# Schematic_final.net
KiCad netlist of a schematic drawn in EAGLE
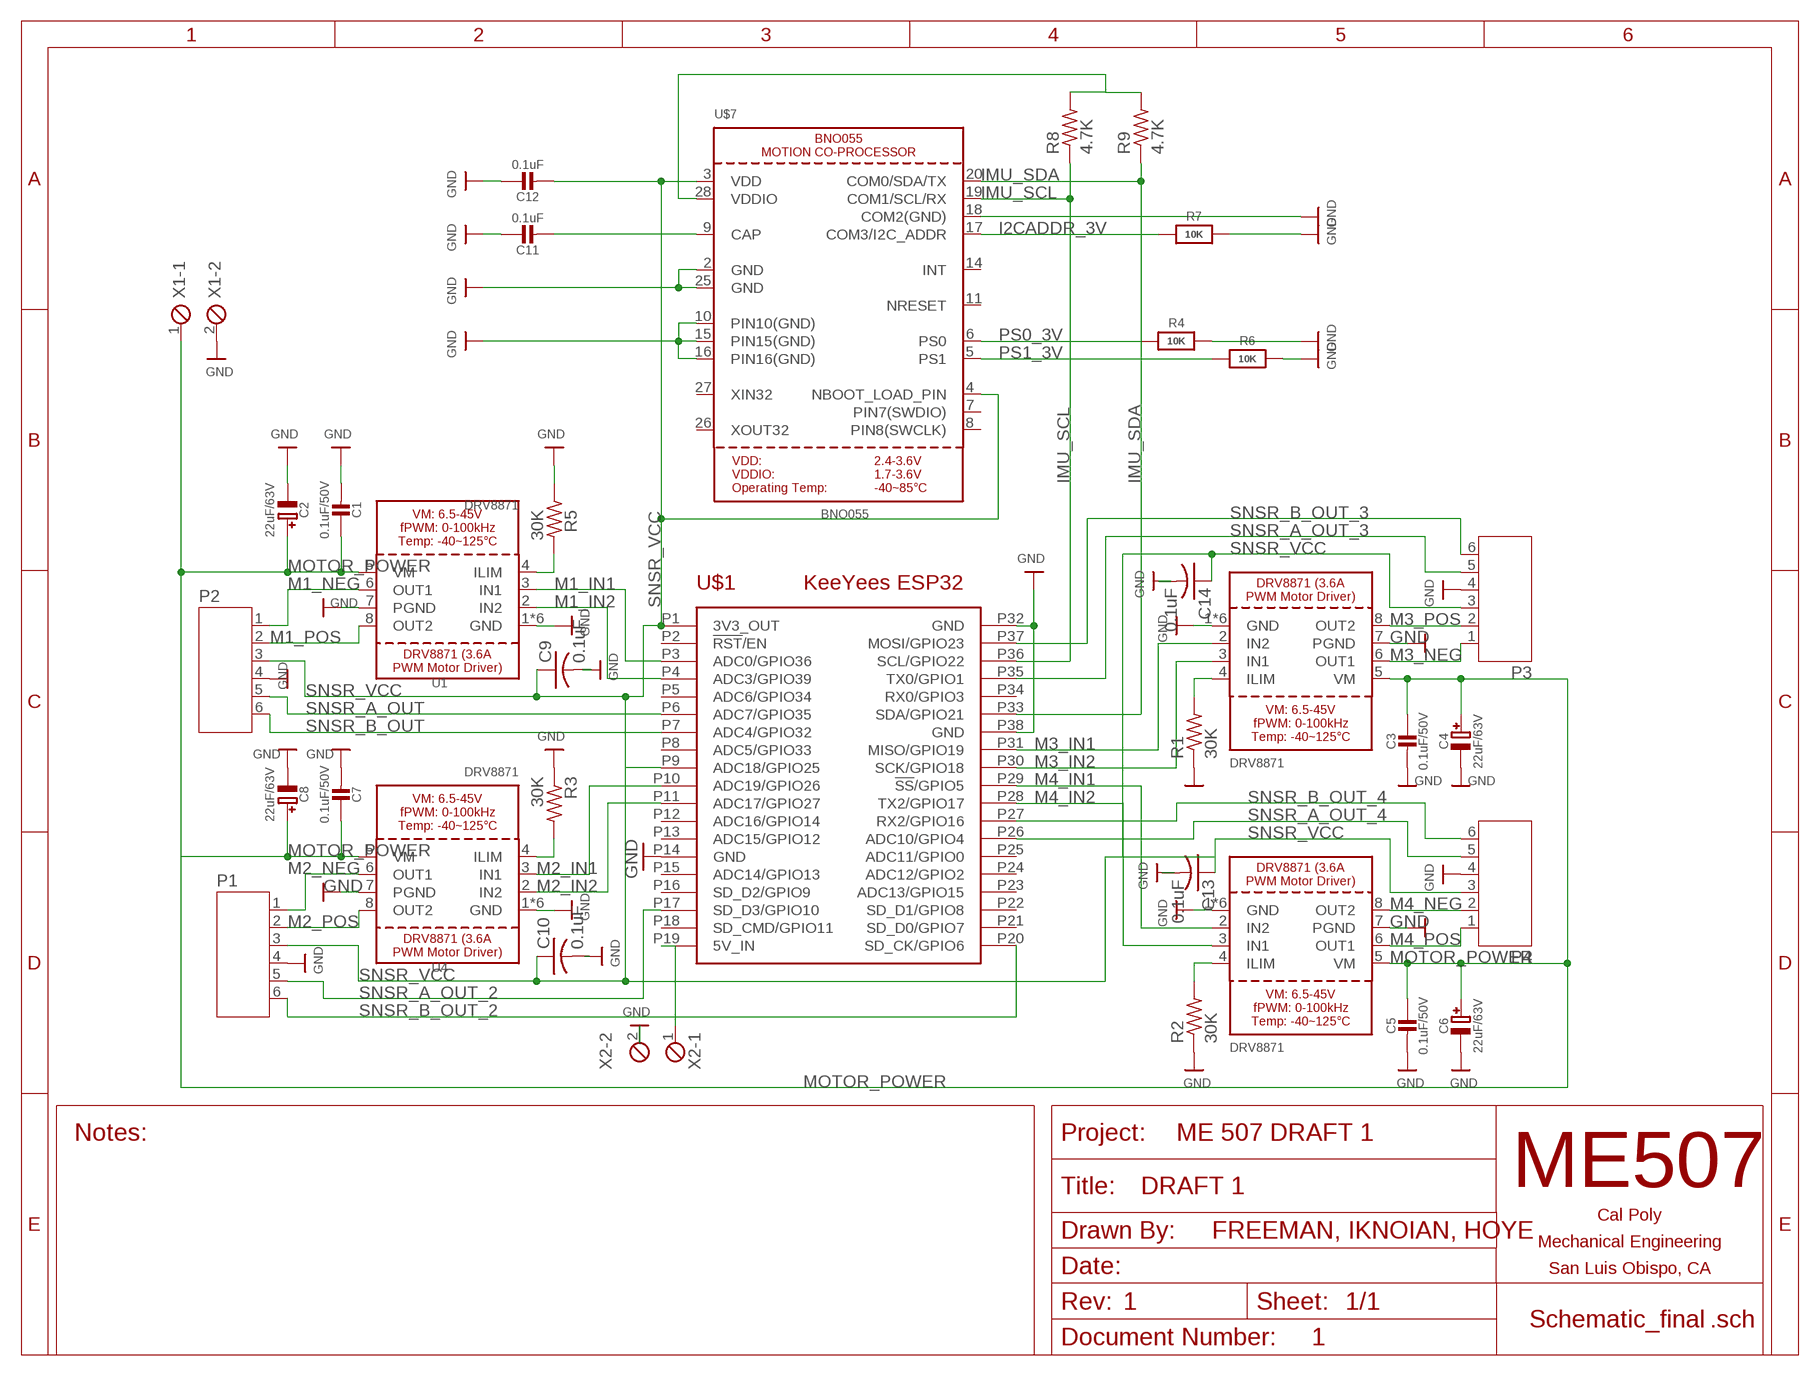
[diagram p0: schematic, sheet 1]

(export (version "E")
  (design (tool "Eeschema 10.0.6"))
  (components
    (comp (ref "C1")
      (value "0.1uF/50V")
      (footprint "eagle-import:0805-NO")
      (libsource (lib "eagle-import") (part "CAP_CERAMIC0805-NOOUTLINE"))
    )
    (comp (ref "C2")
      (value "22uF/63V")
      (footprint "eagle-import:PANASONIC_D")
      (libsource (lib "eagle-import") (part "CAP_ELECTROLYTICPANASONIC_D"))
    )
    (comp (ref "C3")
      (value "0.1uF/50V")
      (footprint "eagle-import:0805-NO")
      (libsource (lib "eagle-import") (part "CAP_CERAMIC0805-NOOUTLINE"))
    )
    (comp (ref "C4")
      (value "22uF/63V")
      (footprint "eagle-import:PANASONIC_D")
      (libsource (lib "eagle-import") (part "CAP_ELECTROLYTICPANASONIC_D"))
    )
    (comp (ref "C5")
      (value "0.1uF/50V")
      (footprint "eagle-import:0805-NO")
      (libsource (lib "eagle-import") (part "CAP_CERAMIC0805-NOOUTLINE"))
    )
    (comp (ref "C6")
      (value "22uF/63V")
      (footprint "eagle-import:PANASONIC_D")
      (libsource (lib "eagle-import") (part "CAP_ELECTROLYTICPANASONIC_D"))
    )
    (comp (ref "C7")
      (value "0.1uF/50V")
      (footprint "eagle-import:0805-NO")
      (libsource (lib "eagle-import") (part "CAP_CERAMIC0805-NOOUTLINE"))
    )
    (comp (ref "C8")
      (value "22uF/63V")
      (footprint "eagle-import:PANASONIC_D")
      (libsource (lib "eagle-import") (part "CAP_ELECTROLYTICPANASONIC_D"))
    )
    (comp (ref "C9")
      (value "0.1uF")
      (footprint "eagle-import:C025-030X050")
      (libsource (lib "eagle-import") (part "C-US025-030X050"))
    )
    (comp (ref "C10")
      (value "0.1uF")
      (footprint "eagle-import:C025-030X050")
      (libsource (lib "eagle-import") (part "C-US025-030X050"))
    )
    (comp (ref "C11")
      (value "0.1uF")
      (footprint "eagle-import:0805-NO")
      (libsource (lib "eagle-import") (part "CAP_CERAMIC0805-NOOUTLINE"))
    )
    (comp (ref "C12")
      (value "0.1uF")
      (footprint "eagle-import:0805_10MGAP")
      (libsource (lib "eagle-import") (part "CAP_CERAMIC0805_10MGAP"))
    )
    (comp (ref "C13")
      (value "0.1uF")
      (footprint "eagle-import:C025-030X050")
      (libsource (lib "eagle-import") (part "C-US025-030X050"))
    )
    (comp (ref "C14")
      (value "0.1uF")
      (footprint "eagle-import:C025-030X050")
      (libsource (lib "eagle-import") (part "C-US025-030X050"))
    )
    (comp (ref "P1")
      (value "JST-PH6")
      (footprint "eagle-import:JST-PH6")
      (libsource (lib "eagle-import") (part "JST-PH6"))
    )
    (comp (ref "P2")
      (value "JST-PH6")
      (footprint "eagle-import:JST-PH6")
      (libsource (lib "eagle-import") (part "JST-PH6"))
    )
    (comp (ref "P3")
      (value "JST-PH6")
      (footprint "eagle-import:JST-PH6")
      (libsource (lib "eagle-import") (part "JST-PH6"))
    )
    (comp (ref "P4")
      (value "JST-PH6")
      (footprint "eagle-import:JST-PH6")
      (libsource (lib "eagle-import") (part "JST-PH6"))
    )
    (comp (ref "R1")
      (value "30K")
      (footprint "eagle-import:0805-THM")
      (libsource (lib "eagle-import") (part "FLIPFLOP-RES"))
    )
    (comp (ref "R2")
      (value "30K")
      (footprint "eagle-import:0805-THM")
      (libsource (lib "eagle-import") (part "FLIPFLOP-RES"))
    )
    (comp (ref "R3")
      (value "30K")
      (footprint "eagle-import:0805-THM")
      (libsource (lib "eagle-import") (part "FLIPFLOP-RES"))
    )
    (comp (ref "R4")
      (value "10K")
      (footprint "eagle-import:0805-NO")
      (libsource (lib "eagle-import") (part "RESISTOR0805_NOOUTLINE"))
    )
    (comp (ref "R5")
      (value "30K")
      (footprint "eagle-import:0805-THM")
      (libsource (lib "eagle-import") (part "FLIPFLOP-RES"))
    )
    (comp (ref "R6")
      (value "10K")
      (footprint "eagle-import:0805-NO")
      (libsource (lib "eagle-import") (part "RESISTOR0805_NOOUTLINE"))
    )
    (comp (ref "R7")
      (value "10K")
      (footprint "eagle-import:0805-NO")
      (libsource (lib "eagle-import") (part "RESISTOR0805_NOOUTLINE"))
    )
    (comp (ref "R8")
      (value "4.7K")
      (footprint "eagle-import:R0805")
      (libsource (lib "eagle-import") (part "R-US_R0805"))
    )
    (comp (ref "R9")
      (value "4.7K")
      (footprint "eagle-import:R0805")
      (libsource (lib "eagle-import") (part "R-US_R0805"))
    )
    (comp (ref "U$1")
      (value "KEEYEES_ESP32")
      (footprint "eagle-import:KEEYEES_ESP32")
      (libsource (lib "eagle-import") (part "KEEYEES_ESP32"))
    )
    (comp (ref "U$7")
      (value "BNO055")
      (footprint "eagle-import:BNO055")
      (libsource (lib "eagle-import") (part "BNO055"))
    )
    (comp (ref "U1")
      (value "DRV8871")
      (footprint "eagle-import:HSOP8")
      (libsource (lib "eagle-import") (part "DRV8871"))
    )
    (comp (ref "U2")
      (value "DRV8871")
      (footprint "eagle-import:HSOP8")
      (libsource (lib "eagle-import") (part "DRV8871"))
    )
    (comp (ref "U3")
      (value "DRV8871")
      (footprint "eagle-import:HSOP8")
      (libsource (lib "eagle-import") (part "DRV8871"))
    )
    (comp (ref "U4")
      (value "DRV8871")
      (footprint "eagle-import:HSOP8")
      (libsource (lib "eagle-import") (part "DRV8871"))
    )
    (comp (ref "X1")
      (value "SCREWTERM_2P_254")
      (footprint "eagle-import:2POL254")
      (libsource (lib "eagle-import") (part "SCREWTERM_2P_254"))
    )
    (comp (ref "X2")
      (value "SCREWTERM_2P_254")
      (footprint "eagle-import:2POL254")
      (libsource (lib "eagle-import") (part "SCREWTERM_2P_254"))
    )
  )
  (nets
    (net (code "1") (name "/I2CADDR_3V") (class "Default")
      (node (ref "R7") (pin "1") (pinfunction "1_1") (pintype "passive"))
      (node (ref "U$7") (pin "17") (pinfunction "COM3/I2C_ADDR_17") (pintype "bidirectional"))
    )
    (net (code "2") (name "/IMU_SCL") (class "Default")
      (node (ref "R8") (pin "1") (pinfunction "1_1") (pintype "passive"))
      (node (ref "U$1") (pin "P36") (pinfunction "SCL/GPIO22_P36") (pintype "bidirectional"))
      (node (ref "U$7") (pin "19") (pinfunction "COM1/SCL/RX_19") (pintype "bidirectional"))
    )
    (net (code "3") (name "/IMU_SDA") (class "Default")
      (node (ref "R9") (pin "1") (pinfunction "1_1") (pintype "passive"))
      (node (ref "U$1") (pin "P33") (pinfunction "SDA/GPIO21_P33") (pintype "bidirectional"))
      (node (ref "U$7") (pin "20") (pinfunction "COM0/SDA/TX_20") (pintype "bidirectional"))
    )
    (net (code "4") (name "/M1_IN1") (class "Default")
      (node (ref "U$1") (pin "P3") (pinfunction "ADC0/GPIO36_P3") (pintype "bidirectional"))
      (node (ref "U1") (pin "3") (pinfunction "IN1_3") (pintype "input"))
    )
    (net (code "5") (name "/M1_IN2") (class "Default")
      (node (ref "U$1") (pin "P4") (pinfunction "ADC3/GPIO39_P4") (pintype "bidirectional"))
      (node (ref "U1") (pin "2") (pinfunction "IN2_2") (pintype "input"))
    )
    (net (code "6") (name "/M1_NEG") (class "Default")
      (node (ref "P2") (pin "1") (pinfunction "1_1") (pintype "passive"))
      (node (ref "U1") (pin "6") (pinfunction "OUT1_6") (pintype "output"))
    )
    (net (code "7") (name "/M1_POS") (class "Default")
      (node (ref "P2") (pin "2") (pinfunction "2_2") (pintype "passive"))
      (node (ref "U1") (pin "8") (pinfunction "OUT2_8") (pintype "output"))
    )
    (net (code "8") (name "/M2_IN1") (class "Default")
      (node (ref "U$1") (pin "P10") (pinfunction "ADC19/GPIO26_P10") (pintype "bidirectional"))
      (node (ref "U4") (pin "3") (pinfunction "IN1_3") (pintype "input"))
    )
    (net (code "9") (name "/M2_IN2") (class "Default")
      (node (ref "U$1") (pin "P11") (pinfunction "ADC17/GPIO27_P11") (pintype "bidirectional"))
      (node (ref "U4") (pin "2") (pinfunction "IN2_2") (pintype "input"))
    )
    (net (code "10") (name "/M2_NEG") (class "Default")
      (node (ref "P1") (pin "1") (pinfunction "1_1") (pintype "passive"))
      (node (ref "U4") (pin "6") (pinfunction "OUT1_6") (pintype "output"))
    )
    (net (code "11") (name "/M2_POS") (class "Default")
      (node (ref "P1") (pin "2") (pinfunction "2_2") (pintype "passive"))
      (node (ref "U4") (pin "8") (pinfunction "OUT2_8") (pintype "output"))
    )
    (net (code "12") (name "/M3_IN1") (class "Default")
      (node (ref "U$1") (pin "P31") (pinfunction "MISO/GPIO19_P31") (pintype "bidirectional"))
      (node (ref "U2") (pin "2") (pinfunction "IN2_2") (pintype "input"))
    )
    (net (code "13") (name "/M3_IN2") (class "Default")
      (node (ref "U$1") (pin "P30") (pinfunction "SCK/GPIO18_P30") (pintype "bidirectional"))
      (node (ref "U2") (pin "3") (pinfunction "IN1_3") (pintype "input"))
    )
    (net (code "14") (name "/M3_NEG") (class "Default")
      (node (ref "P3") (pin "1") (pinfunction "1_1") (pintype "passive"))
      (node (ref "U2") (pin "6") (pinfunction "OUT1_6") (pintype "output"))
    )
    (net (code "15") (name "/M3_POS") (class "Default")
      (node (ref "P3") (pin "2") (pinfunction "2_2") (pintype "passive"))
      (node (ref "U2") (pin "8") (pinfunction "OUT2_8") (pintype "output"))
    )
    (net (code "16") (name "/M4_IN1") (class "Default")
      (node (ref "U$1") (pin "P29") (pinfunction "~{SS}/GPIO5_P29") (pintype "bidirectional"))
      (node (ref "U3") (pin "2") (pinfunction "IN2_2") (pintype "input"))
    )
    (net (code "17") (name "/M4_IN2") (class "Default")
      (node (ref "U$1") (pin "P28") (pinfunction "TX2/GPIO17_P28") (pintype "bidirectional"))
      (node (ref "U3") (pin "3") (pinfunction "IN1_3") (pintype "input"))
    )
    (net (code "18") (name "/M4_NEG") (class "Default")
      (node (ref "P4") (pin "2") (pinfunction "2_2") (pintype "passive"))
      (node (ref "U3") (pin "8") (pinfunction "OUT2_8") (pintype "output"))
    )
    (net (code "19") (name "/M4_POS") (class "Default")
      (node (ref "P4") (pin "1") (pinfunction "1_1") (pintype "passive"))
      (node (ref "U3") (pin "6") (pinfunction "OUT1_6") (pintype "output"))
    )
    (net (code "20") (name "/MOTOR_POWER") (class "Default")
      (node (ref "C1") (pin "1") (pinfunction "1_1") (pintype "passive"))
      (node (ref "C2") (pin "+") (pinfunction "+_+") (pintype "passive"))
      (node (ref "C3") (pin "1") (pinfunction "1_1") (pintype "passive"))
      (node (ref "C4") (pin "+") (pinfunction "+_+") (pintype "passive"))
      (node (ref "C5") (pin "1") (pinfunction "1_1") (pintype "passive"))
      (node (ref "C6") (pin "+") (pinfunction "+_+") (pintype "passive"))
      (node (ref "C7") (pin "1") (pinfunction "1_1") (pintype "passive"))
      (node (ref "C8") (pin "+") (pinfunction "+_+") (pintype "passive"))
      (node (ref "U1") (pin "5") (pinfunction "VM_5") (pintype "power_in"))
      (node (ref "U2") (pin "5") (pinfunction "VM_5") (pintype "power_in"))
      (node (ref "U3") (pin "5") (pinfunction "VM_5") (pintype "power_in"))
      (node (ref "U4") (pin "5") (pinfunction "VM_5") (pintype "power_in"))
      (node (ref "X1") (pin "1") (pinfunction "1_1") (pintype "passive"))
    )
    (net (code "21") (name "/PS0_3V") (class "Default")
      (node (ref "R4") (pin "1") (pinfunction "1_1") (pintype "passive"))
      (node (ref "U$7") (pin "6") (pinfunction "PS0_6") (pintype "input"))
    )
    (net (code "22") (name "/PS1_3V") (class "Default")
      (node (ref "R6") (pin "1") (pinfunction "1_1") (pintype "passive"))
      (node (ref "U$7") (pin "5") (pinfunction "PS1_5") (pintype "input"))
    )
    (net (code "23") (name "/SNSR_A_OUT") (class "Default")
      (node (ref "P2") (pin "5") (pinfunction "5_5") (pintype "passive"))
      (node (ref "U$1") (pin "P6") (pinfunction "ADC7/GPIO35_P6") (pintype "bidirectional"))
    )
    (net (code "24") (name "/SNSR_A_OUT_2") (class "Default")
      (node (ref "P1") (pin "5") (pinfunction "5_5") (pintype "passive"))
      (node (ref "U$1") (pin "P17") (pinfunction "SD_D3/GPIO10_P17") (pintype "bidirectional"))
    )
    (net (code "25") (name "/SNSR_A_OUT_3") (class "Default")
      (node (ref "P3") (pin "5") (pinfunction "5_5") (pintype "passive"))
      (node (ref "U$1") (pin "P35") (pinfunction "TX0/GPIO1_P35") (pintype "bidirectional"))
    )
    (net (code "26") (name "/SNSR_A_OUT_4") (class "Default")
      (node (ref "P4") (pin "5") (pinfunction "5_5") (pintype "passive"))
      (node (ref "U$1") (pin "P26") (pinfunction "ADC10/GPIO4_P26") (pintype "bidirectional"))
    )
    (net (code "27") (name "/SNSR_B_OUT") (class "Default")
      (node (ref "P2") (pin "6") (pinfunction "6_6") (pintype "passive"))
      (node (ref "U$1") (pin "P7") (pinfunction "ADC4/GPIO32_P7") (pintype "bidirectional"))
    )
    (net (code "28") (name "/SNSR_B_OUT_2") (class "Default")
      (node (ref "P1") (pin "6") (pinfunction "6_6") (pintype "passive"))
      (node (ref "U$1") (pin "P20") (pinfunction "SD_CK/GPIO6_P20") (pintype "bidirectional"))
    )
    (net (code "29") (name "/SNSR_B_OUT_3") (class "Default")
      (node (ref "P3") (pin "6") (pinfunction "6_6") (pintype "passive"))
      (node (ref "U$1") (pin "P37") (pinfunction "MOSI/GPIO23_P37") (pintype "bidirectional"))
    )
    (net (code "30") (name "/SNSR_B_OUT_4") (class "Default")
      (node (ref "P4") (pin "6") (pinfunction "6_6") (pintype "passive"))
      (node (ref "U$1") (pin "P27") (pinfunction "RX2/GPIO16_P27") (pintype "bidirectional"))
    )
    (net (code "31") (name "/SNSR_VCC") (class "Default")
      (node (ref "C10") (pin "1") (pinfunction "1_1") (pintype "passive"))
      (node (ref "C12") (pin "2") (pinfunction "2_2") (pintype "passive"))
      (node (ref "C13") (pin "1") (pinfunction "1_1") (pintype "passive"))
      (node (ref "C14") (pin "1") (pinfunction "1_1") (pintype "passive"))
      (node (ref "C9") (pin "1") (pinfunction "1_1") (pintype "passive"))
      (node (ref "P1") (pin "3") (pinfunction "3_3") (pintype "passive"))
      (node (ref "P2") (pin "3") (pinfunction "3_3") (pintype "passive"))
      (node (ref "P3") (pin "3") (pinfunction "3_3") (pintype "passive"))
      (node (ref "P4") (pin "3") (pinfunction "3_3") (pintype "passive"))
      (node (ref "U$1") (pin "P1") (pinfunction "3V3_OUT_P1") (pintype "power_in"))
      (node (ref "U$7") (pin "3") (pinfunction "VDD_3") (pintype "power_in"))
      (node (ref "U$7") (pin "4") (pinfunction "NBOOT_LOAD_PIN_4") (pintype "bidirectional"))
    )
    (net (code "32") (name "GND") (class "Default")
      (node (ref "C1") (pin "2") (pinfunction "2_2") (pintype "passive"))
      (node (ref "C10") (pin "2") (pinfunction "2_2") (pintype "passive"))
      (node (ref "C11") (pin "1") (pinfunction "1_1") (pintype "passive"))
      (node (ref "C12") (pin "1") (pinfunction "1_1") (pintype "passive"))
      (node (ref "C13") (pin "2") (pinfunction "2_2") (pintype "passive"))
      (node (ref "C14") (pin "2") (pinfunction "2_2") (pintype "passive"))
      (node (ref "C2") (pin "-") (pinfunction "-_-") (pintype "passive"))
      (node (ref "C3") (pin "2") (pinfunction "2_2") (pintype "passive"))
      (node (ref "C4") (pin "-") (pinfunction "-_-") (pintype "passive"))
      (node (ref "C5") (pin "2") (pinfunction "2_2") (pintype "passive"))
      (node (ref "C6") (pin "-") (pinfunction "-_-") (pintype "passive"))
      (node (ref "C7") (pin "2") (pinfunction "2_2") (pintype "passive"))
      (node (ref "C8") (pin "-") (pinfunction "-_-") (pintype "passive"))
      (node (ref "C9") (pin "2") (pinfunction "2_2") (pintype "passive"))
      (node (ref "P1") (pin "4") (pinfunction "4_4") (pintype "passive"))
      (node (ref "P2") (pin "4") (pinfunction "4_4") (pintype "passive"))
      (node (ref "P3") (pin "4") (pinfunction "4_4") (pintype "passive"))
      (node (ref "P4") (pin "4") (pinfunction "4_4") (pintype "passive"))
      (node (ref "R1") (pin "1") (pinfunction "1_1") (pintype "passive"))
      (node (ref "R2") (pin "1") (pinfunction "1_1") (pintype "passive"))
      (node (ref "R3") (pin "1") (pinfunction "1_1") (pintype "passive"))
      (node (ref "R4") (pin "2") (pinfunction "2_2") (pintype "passive"))
      (node (ref "R5") (pin "1") (pinfunction "1_1") (pintype "passive"))
      (node (ref "R6") (pin "2") (pinfunction "2_2") (pintype "passive"))
      (node (ref "R7") (pin "2") (pinfunction "2_2") (pintype "passive"))
      (node (ref "U$1") (pin "P14") (pinfunction "GND_P14") (pintype "power_in"))
      (node (ref "U$1") (pin "P32") (pinfunction "GND_P32") (pintype "power_in"))
      (node (ref "U$1") (pin "P38") (pinfunction "GND_P38") (pintype "power_in"))
      (node (ref "U$7") (pin "10") (pinfunction "PIN10(GND)_10") (pintype "bidirectional"))
      (node (ref "U$7") (pin "15") (pinfunction "PIN15(GND)_15") (pintype "bidirectional"))
      (node (ref "U$7") (pin "16") (pinfunction "PIN16(GND)_16") (pintype "bidirectional"))
      (node (ref "U$7") (pin "18") (pinfunction "COM2(GND)_18") (pintype "bidirectional"))
      (node (ref "U$7") (pin "2") (pinfunction "GND_2") (pintype "power_in"))
      (node (ref "U$7") (pin "25") (pinfunction "GND_25") (pintype "power_in"))
      (node (ref "U1") (pin "1") (pinfunction "GND_1") (pintype "power_in"))
      (node (ref "U1") (pin "7") (pinfunction "PGND_7") (pintype "power_in"))
      (node (ref "U1") (pin "GND") (pinfunction "GND_GND") (pintype "power_in"))
      (node (ref "U1") (pin "P$1") (pinfunction "GND_P$1") (pintype "power_in"))
      (node (ref "U1") (pin "P$2") (pinfunction "GND_P$2") (pintype "power_in"))
      (node (ref "U1") (pin "P$3") (pinfunction "GND_P$3") (pintype "power_in"))
      (node (ref "U1") (pin "P$4") (pinfunction "GND_P$4") (pintype "power_in"))
      (node (ref "U2") (pin "1") (pinfunction "GND_1") (pintype "power_in"))
      (node (ref "U2") (pin "7") (pinfunction "PGND_7") (pintype "power_in"))
      (node (ref "U2") (pin "GND") (pinfunction "GND_GND") (pintype "power_in"))
      (node (ref "U2") (pin "P$1") (pinfunction "GND_P$1") (pintype "power_in"))
      (node (ref "U2") (pin "P$2") (pinfunction "GND_P$2") (pintype "power_in"))
      (node (ref "U2") (pin "P$3") (pinfunction "GND_P$3") (pintype "power_in"))
      (node (ref "U2") (pin "P$4") (pinfunction "GND_P$4") (pintype "power_in"))
      (node (ref "U3") (pin "1") (pinfunction "GND_1") (pintype "power_in"))
      (node (ref "U3") (pin "7") (pinfunction "PGND_7") (pintype "power_in"))
      (node (ref "U3") (pin "GND") (pinfunction "GND_GND") (pintype "power_in"))
      (node (ref "U3") (pin "P$1") (pinfunction "GND_P$1") (pintype "power_in"))
      (node (ref "U3") (pin "P$2") (pinfunction "GND_P$2") (pintype "power_in"))
      (node (ref "U3") (pin "P$3") (pinfunction "GND_P$3") (pintype "power_in"))
      (node (ref "U3") (pin "P$4") (pinfunction "GND_P$4") (pintype "power_in"))
      (node (ref "U4") (pin "1") (pinfunction "GND_1") (pintype "power_in"))
      (node (ref "U4") (pin "7") (pinfunction "PGND_7") (pintype "power_in"))
      (node (ref "U4") (pin "GND") (pinfunction "GND_GND") (pintype "power_in"))
      (node (ref "U4") (pin "P$1") (pinfunction "GND_P$1") (pintype "power_in"))
      (node (ref "U4") (pin "P$2") (pinfunction "GND_P$2") (pintype "power_in"))
      (node (ref "U4") (pin "P$3") (pinfunction "GND_P$3") (pintype "power_in"))
      (node (ref "U4") (pin "P$4") (pinfunction "GND_P$4") (pintype "power_in"))
      (node (ref "X1") (pin "2") (pinfunction "1_2") (pintype "passive"))
      (node (ref "X2") (pin "2") (pinfunction "1_2") (pintype "passive"))
    )
    (net (code "33") (name "Net-(U$1-5V_IN)") (class "Default")
      (node (ref "U$1") (pin "P19") (pinfunction "5V_IN_P19") (pintype "power_in"))
      (node (ref "X2") (pin "1") (pinfunction "1_1") (pintype "passive"))
    )
    (net (code "34") (name "Net-(U$7-CAP)") (class "Default")
      (node (ref "C11") (pin "2") (pinfunction "2_2") (pintype "passive"))
      (node (ref "U$7") (pin "9") (pinfunction "CAP_9") (pintype "passive"))
    )
    (net (code "35") (name "Net-(U$7-VDDIO)") (class "Default")
      (node (ref "R8") (pin "2") (pinfunction "2_2") (pintype "passive"))
      (node (ref "R9") (pin "2") (pinfunction "2_2") (pintype "passive"))
      (node (ref "U$7") (pin "28") (pinfunction "VDDIO_28") (pintype "power_in"))
    )
    (net (code "36") (name "Net-(U1-ILIM)") (class "Default")
      (node (ref "R5") (pin "2") (pinfunction "2_2") (pintype "passive"))
      (node (ref "U1") (pin "4") (pinfunction "ILIM_4") (pintype "input"))
    )
    (net (code "37") (name "Net-(U2-ILIM)") (class "Default")
      (node (ref "R1") (pin "2") (pinfunction "2_2") (pintype "passive"))
      (node (ref "U2") (pin "4") (pinfunction "ILIM_4") (pintype "input"))
    )
    (net (code "38") (name "Net-(U3-ILIM)") (class "Default")
      (node (ref "R2") (pin "2") (pinfunction "2_2") (pintype "passive"))
      (node (ref "U3") (pin "4") (pinfunction "ILIM_4") (pintype "input"))
    )
    (net (code "39") (name "Net-(U4-ILIM)") (class "Default")
      (node (ref "R3") (pin "2") (pinfunction "2_2") (pintype "passive"))
      (node (ref "U4") (pin "4") (pinfunction "ILIM_4") (pintype "input"))
    )
    (net (code "40") (name "unconnected-(U$1-ADC5{slash}GPIO33-PadP8)") (class "Default")
      (node (ref "U$1") (pin "P8") (pinfunction "ADC5/GPIO33_P8") (pintype "bidirectional"))
    )
    (net (code "41") (name "unconnected-(U$1-ADC6{slash}GPIO34-PadP5)") (class "Default")
      (node (ref "U$1") (pin "P5") (pinfunction "ADC6/GPIO34_P5") (pintype "bidirectional"))
    )
    (net (code "42") (name "unconnected-(U$1-ADC11{slash}GPIO0-PadP25)") (class "Default")
      (node (ref "U$1") (pin "P25") (pinfunction "ADC11/GPIO0_P25") (pintype "bidirectional"))
    )
    (net (code "43") (name "unconnected-(U$1-ADC12{slash}GPIO2-PadP24)") (class "Default")
      (node (ref "U$1") (pin "P24") (pinfunction "ADC12/GPIO2_P24") (pintype "bidirectional"))
    )
    (net (code "44") (name "unconnected-(U$1-ADC13{slash}GPIO15-PadP23)") (class "Default")
      (node (ref "U$1") (pin "P23") (pinfunction "ADC13/GPIO15_P23") (pintype "bidirectional"))
    )
    (net (code "45") (name "unconnected-(U$1-ADC14{slash}GPIO13-PadP15)") (class "Default")
      (node (ref "U$1") (pin "P15") (pinfunction "ADC14/GPIO13_P15") (pintype "bidirectional"))
    )
    (net (code "46") (name "unconnected-(U$1-ADC15{slash}GPIO12-PadP13)") (class "Default")
      (node (ref "U$1") (pin "P13") (pinfunction "ADC15/GPIO12_P13") (pintype "bidirectional"))
    )
    (net (code "47") (name "unconnected-(U$1-ADC16{slash}GPIO14-PadP12)") (class "Default")
      (node (ref "U$1") (pin "P12") (pinfunction "ADC16/GPIO14_P12") (pintype "bidirectional"))
    )
    (net (code "48") (name "unconnected-(U$1-ADC18{slash}GPIO25-PadP9)") (class "Default")
      (node (ref "U$1") (pin "P9") (pinfunction "ADC18/GPIO25_P9") (pintype "bidirectional"))
    )
    (net (code "49") (name "unconnected-(U$1-RX0{slash}GPIO3-PadP34)") (class "Default")
      (node (ref "U$1") (pin "P34") (pinfunction "RX0/GPIO3_P34") (pintype "bidirectional"))
    )
    (net (code "50") (name "unconnected-(U$1-SD_CMD{slash}GPIO11-PadP18)") (class "Default")
      (node (ref "U$1") (pin "P18") (pinfunction "SD_CMD/GPIO11_P18") (pintype "bidirectional"))
    )
    (net (code "51") (name "unconnected-(U$1-SD_D0{slash}GPIO7-PadP21)") (class "Default")
      (node (ref "U$1") (pin "P21") (pinfunction "SD_D0/GPIO7_P21") (pintype "bidirectional"))
    )
    (net (code "52") (name "unconnected-(U$1-SD_D1{slash}GPIO8-PadP22)") (class "Default")
      (node (ref "U$1") (pin "P22") (pinfunction "SD_D1/GPIO8_P22") (pintype "bidirectional"))
    )
    (net (code "53") (name "unconnected-(U$1-SD_D2{slash}GPIO9-PadP16)") (class "Default")
      (node (ref "U$1") (pin "P16") (pinfunction "SD_D2/GPIO9_P16") (pintype "bidirectional"))
    )
    (net (code "54") (name "unconnected-(U$1-~{RST}{slash}EN-PadP2)") (class "Default")
      (node (ref "U$1") (pin "P2") (pinfunction "~{RST}/EN_P2") (pintype "input"))
    )
    (net (code "55") (name "unconnected-(U$7-INT-Pad14)") (class "Default")
      (node (ref "U$7") (pin "14") (pinfunction "INT_14") (pintype "output"))
    )
    (net (code "56") (name "unconnected-(U$7-NRESET-Pad11)") (class "Default")
      (node (ref "U$7") (pin "11") (pinfunction "NRESET_11") (pintype "bidirectional"))
    )
    (net (code "57") (name "unconnected-(U$7-PIN7(SWDIO)-Pad7)") (class "Default")
      (node (ref "U$7") (pin "7") (pinfunction "PIN7(SWDIO)_7") (pintype "bidirectional"))
    )
    (net (code "58") (name "unconnected-(U$7-PIN8(SWCLK)-Pad8)") (class "Default")
      (node (ref "U$7") (pin "8") (pinfunction "PIN8(SWCLK)_8") (pintype "bidirectional"))
    )
    (net (code "59") (name "unconnected-(U$7-XIN32-Pad27)") (class "Default")
      (node (ref "U$7") (pin "27") (pinfunction "XIN32_27") (pintype "input"))
    )
    (net (code "60") (name "unconnected-(U$7-XOUT32-Pad26)") (class "Default")
      (node (ref "U$7") (pin "26") (pinfunction "XOUT32_26") (pintype "output"))
    )
  )
)
